# SmartWatch-Basic-Bottom.net
KiCad netlist of a schematic drawn in EAGLE
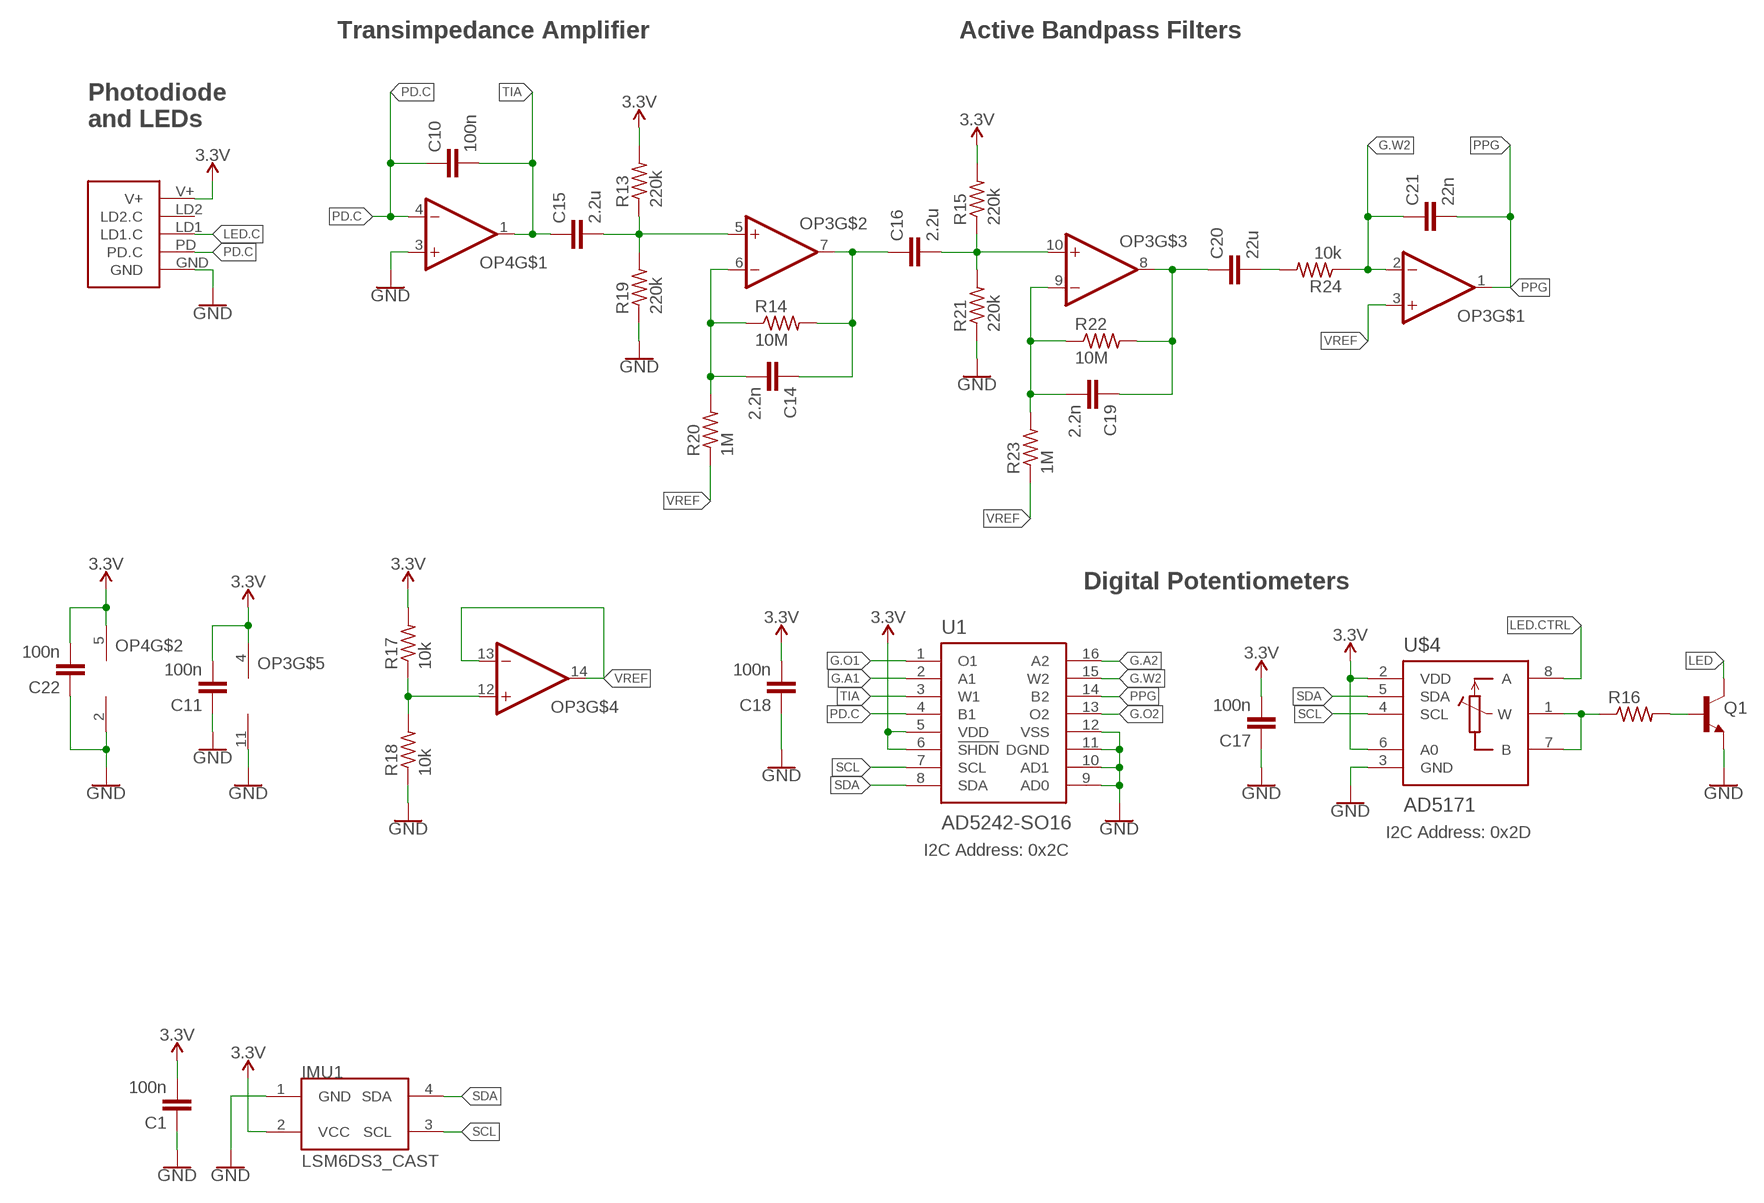
[diagram p0: schematic, sheet 1]

(export (version "E")
  (design (tool "Eeschema 10.0.6"))
  (components
    (comp (ref "C1")
      (value "100n")
      (footprint "eagle-import:C0603")
      (libsource (lib "eagle-import") (part "CAPACITOR0603"))
    )
    (comp (ref "C10")
      (value "100n")
      (footprint "eagle-import:C0603")
      (libsource (lib "eagle-import") (part "CAPACITOR0603"))
    )
    (comp (ref "C11")
      (value "100n")
      (footprint "eagle-import:C0603")
      (libsource (lib "eagle-import") (part "CAPACITOR0603"))
    )
    (comp (ref "C14")
      (value "2.2n")
      (footprint "eagle-import:C0603")
      (libsource (lib "eagle-import") (part "CAPACITOR0603"))
    )
    (comp (ref "C15")
      (value "2.2u")
      (footprint "eagle-import:C0603")
      (libsource (lib "eagle-import") (part "CAPACITOR0603"))
    )
    (comp (ref "C16")
      (value "2.2u")
      (footprint "eagle-import:C0603")
      (libsource (lib "eagle-import") (part "CAPACITOR0603"))
    )
    (comp (ref "C17")
      (value "100n")
      (footprint "eagle-import:C0603")
      (libsource (lib "eagle-import") (part "CAPACITOR0603"))
    )
    (comp (ref "C18")
      (value "100n")
      (footprint "eagle-import:C0603")
      (libsource (lib "eagle-import") (part "CAPACITOR0603"))
    )
    (comp (ref "C19")
      (value "2.2n")
      (footprint "eagle-import:C0603")
      (libsource (lib "eagle-import") (part "CAPACITOR0603"))
    )
    (comp (ref "C20")
      (value "22u")
      (footprint "eagle-import:C0603")
      (libsource (lib "eagle-import") (part "CAPACITOR0603"))
    )
    (comp (ref "C21")
      (value "22n")
      (footprint "eagle-import:C0603")
      (libsource (lib "eagle-import") (part "CAPACITOR0603"))
    )
    (comp (ref "C22")
      (value "100n")
      (footprint "eagle-import:C0603")
      (libsource (lib "eagle-import") (part "CAPACITOR0603"))
    )
    (comp (ref "IMU1")
      (value "LSM6DS3_CAST")
      (footprint "eagle-import:LSM6DS3_CAST")
      (libsource (lib "eagle-import") (part "LSM6DS3_CAST"))
    )
    (comp (ref "OP3")
      (value "OP-QUAD-SO14")
      (footprint "eagle-import:SO14")
      (libsource (lib "eagle-import") (part "OP-QUAD-SO14"))
    )
    (comp (ref "OP4")
      (value "OP-SINGLEOT")
      (footprint "eagle-import:SOT23-5")
      (libsource (lib "eagle-import") (part "OP-SINGLEOT"))
    )
    (comp (ref "Q1")
      (value "NPN-GENERIC")
      (footprint "eagle-import:SOT23-3")
      (libsource (lib "eagle-import") (part "NPN-GENERIC"))
    )
    (comp (ref "R13")
      (value "220k")
      (footprint "eagle-import:R0603")
      (libsource (lib "eagle-import") (part "RESISTOR0603"))
    )
    (comp (ref "R14")
      (value "10M")
      (footprint "eagle-import:R0603")
      (libsource (lib "eagle-import") (part "RESISTOR0603"))
    )
    (comp (ref "R15")
      (value "220k")
      (footprint "eagle-import:R0603")
      (libsource (lib "eagle-import") (part "RESISTOR0603"))
    )
    (comp (ref "R16")
      (value "RESISTOR0603")
      (footprint "eagle-import:R0603")
      (libsource (lib "eagle-import") (part "RESISTOR0603"))
    )
    (comp (ref "R17")
      (value "10k")
      (footprint "eagle-import:R0402")
      (libsource (lib "eagle-import") (part "RESISTOR0402"))
    )
    (comp (ref "R18")
      (value "10k")
      (footprint "eagle-import:R0402")
      (libsource (lib "eagle-import") (part "RESISTOR0402"))
    )
    (comp (ref "R19")
      (value "220k")
      (footprint "eagle-import:R0603")
      (libsource (lib "eagle-import") (part "RESISTOR0603"))
    )
    (comp (ref "R20")
      (value "1M")
      (footprint "eagle-import:R0603")
      (libsource (lib "eagle-import") (part "RESISTOR0603"))
    )
    (comp (ref "R21")
      (value "220k")
      (footprint "eagle-import:R0603")
      (libsource (lib "eagle-import") (part "RESISTOR0603"))
    )
    (comp (ref "R22")
      (value "10M")
      (footprint "eagle-import:R0603")
      (libsource (lib "eagle-import") (part "RESISTOR0603"))
    )
    (comp (ref "R23")
      (value "1M")
      (footprint "eagle-import:R0603")
      (libsource (lib "eagle-import") (part "RESISTOR0603"))
    )
    (comp (ref "R24")
      (value "10k")
      (footprint "eagle-import:R0603")
      (libsource (lib "eagle-import") (part "RESISTOR0603"))
    )
    (comp (ref "U$3")
      (value "PPG.MODULE.2")
      (footprint "eagle-import:PPG.MODULE.2")
      (libsource (lib "eagle-import") (part "PPG.MODULE.2"))
    )
    (comp (ref "U$4")
      (value "AD5171")
      (footprint "eagle-import:SOT-23-8")
      (libsource (lib "eagle-import") (part "AD5171"))
    )
    (comp (ref "U1")
      (value "AD5242-SO16")
      (footprint "eagle-import:SO16")
      (libsource (lib "eagle-import") (part "AD5242-SO16"))
    )
  )
  (nets
    (net (code "1") (name "3.3V") (class "Default")
      (node (ref "C1") (pin "2") (pinfunction "2_2") (pintype "passive"))
      (node (ref "C11") (pin "2") (pinfunction "2_2") (pintype "passive"))
      (node (ref "C17") (pin "2") (pinfunction "2_2") (pintype "passive"))
      (node (ref "C18") (pin "2") (pinfunction "2_2") (pintype "passive"))
      (node (ref "C22") (pin "2") (pinfunction "2_2") (pintype "passive"))
      (node (ref "IMU1") (pin "2") (pinfunction "VCC_2") (pintype "bidirectional"))
      (node (ref "OP3") (pin "4") (pinfunction "V+_4") (pintype "power_in"))
      (node (ref "OP4") (pin "5") (pinfunction "V+_5") (pintype "power_in"))
      (node (ref "R13") (pin "2") (pinfunction "2_2") (pintype "passive"))
      (node (ref "R15") (pin "2") (pinfunction "2_2") (pintype "passive"))
      (node (ref "R17") (pin "2") (pinfunction "2_2") (pintype "passive"))
      (node (ref "U$3") (pin "V+") (pinfunction "V+_V+") (pintype "bidirectional"))
      (node (ref "U$4") (pin "2") (pinfunction "VDD_2") (pintype "bidirectional"))
      (node (ref "U$4") (pin "6") (pinfunction "A0_6") (pintype "bidirectional"))
      (node (ref "U1") (pin "5") (pinfunction "VDD_5") (pintype "bidirectional"))
      (node (ref "U1") (pin "6") (pinfunction "~{SHDN}_6") (pintype "bidirectional"))
    )
    (net (code "2") (name "G.A1") (class "Default")
      (node (ref "U1") (pin "2") (pinfunction "A1_2") (pintype "bidirectional"))
    )
    (net (code "3") (name "G.A2") (class "Default")
      (node (ref "U1") (pin "16") (pinfunction "A2_16") (pintype "bidirectional"))
    )
    (net (code "4") (name "G.O1") (class "Default")
      (node (ref "U1") (pin "1") (pinfunction "O1_1") (pintype "bidirectional"))
    )
    (net (code "5") (name "G.O2") (class "Default")
      (node (ref "U1") (pin "13") (pinfunction "O2_13") (pintype "bidirectional"))
    )
    (net (code "6") (name "G.W2") (class "Default")
      (node (ref "C21") (pin "1") (pinfunction "1_1") (pintype "passive"))
      (node (ref "OP3") (pin "2") (pinfunction "-IN_2") (pintype "input"))
      (node (ref "R24") (pin "1") (pinfunction "1_1") (pintype "passive"))
      (node (ref "U1") (pin "15") (pinfunction "W2_15") (pintype "bidirectional"))
    )
    (net (code "7") (name "GND") (class "Default")
      (node (ref "C1") (pin "1") (pinfunction "1_1") (pintype "passive"))
      (node (ref "C11") (pin "1") (pinfunction "1_1") (pintype "passive"))
      (node (ref "C17") (pin "1") (pinfunction "1_1") (pintype "passive"))
      (node (ref "C18") (pin "1") (pinfunction "1_1") (pintype "passive"))
      (node (ref "C22") (pin "1") (pinfunction "1_1") (pintype "passive"))
      (node (ref "IMU1") (pin "1") (pinfunction "GND_1") (pintype "bidirectional"))
      (node (ref "OP3") (pin "11") (pinfunction "V-_11") (pintype "power_in"))
      (node (ref "OP4") (pin "2") (pinfunction "V-_2") (pintype "power_in"))
      (node (ref "OP4") (pin "3") (pinfunction "+IN_3") (pintype "input"))
      (node (ref "Q1") (pin "2") (pinfunction "E_2") (pintype "passive"))
      (node (ref "R18") (pin "1") (pinfunction "1_1") (pintype "passive"))
      (node (ref "R19") (pin "1") (pinfunction "1_1") (pintype "passive"))
      (node (ref "R21") (pin "1") (pinfunction "1_1") (pintype "passive"))
      (node (ref "U$3") (pin "GND") (pinfunction "GND_GND") (pintype "bidirectional"))
      (node (ref "U$4") (pin "3") (pinfunction "GND_3") (pintype "bidirectional"))
      (node (ref "U1") (pin "10") (pinfunction "AD1_10") (pintype "bidirectional"))
      (node (ref "U1") (pin "11") (pinfunction "DGND_11") (pintype "bidirectional"))
      (node (ref "U1") (pin "12") (pinfunction "VSS_12") (pintype "bidirectional"))
      (node (ref "U1") (pin "9") (pinfunction "AD0_9") (pintype "bidirectional"))
    )
    (net (code "8") (name "LED") (class "Default")
      (node (ref "Q1") (pin "3") (pinfunction "C_3") (pintype "passive"))
    )
    (net (code "9") (name "LED.C") (class "Default")
      (node (ref "U$3") (pin "LD1") (pinfunction "LD1.C_LD1") (pintype "bidirectional"))
    )
    (net (code "10") (name "LED.CTRL") (class "Default")
      (node (ref "U$4") (pin "8") (pinfunction "A_8") (pintype "bidirectional"))
    )
    (net (code "11") (name "Net-(C20-Pad2)") (class "Default")
      (node (ref "C20") (pin "2") (pinfunction "2_2") (pintype "passive"))
      (node (ref "R24") (pin "2") (pinfunction "2_2") (pintype "passive"))
    )
    (net (code "12") (name "Net-(OP3B-+IN)") (class "Default")
      (node (ref "C15") (pin "2") (pinfunction "2_2") (pintype "passive"))
      (node (ref "OP3") (pin "5") (pinfunction "+IN_5") (pintype "input"))
      (node (ref "R13") (pin "1") (pinfunction "1_1") (pintype "passive"))
      (node (ref "R19") (pin "2") (pinfunction "2_2") (pintype "passive"))
    )
    (net (code "13") (name "Net-(OP3B--IN)") (class "Default")
      (node (ref "C14") (pin "2") (pinfunction "2_2") (pintype "passive"))
      (node (ref "OP3") (pin "6") (pinfunction "-IN_6") (pintype "input"))
      (node (ref "R14") (pin "1") (pinfunction "1_1") (pintype "passive"))
      (node (ref "R20") (pin "2") (pinfunction "2_2") (pintype "passive"))
    )
    (net (code "14") (name "Net-(OP3B-OUT)") (class "Default")
      (node (ref "C14") (pin "1") (pinfunction "1_1") (pintype "passive"))
      (node (ref "C16") (pin "1") (pinfunction "1_1") (pintype "passive"))
      (node (ref "OP3") (pin "7") (pinfunction "OUT_7") (pintype "output"))
      (node (ref "R14") (pin "2") (pinfunction "2_2") (pintype "passive"))
    )
    (net (code "15") (name "Net-(OP3C-+IN)") (class "Default")
      (node (ref "C16") (pin "2") (pinfunction "2_2") (pintype "passive"))
      (node (ref "OP3") (pin "10") (pinfunction "+IN_10") (pintype "input"))
      (node (ref "R15") (pin "1") (pinfunction "1_1") (pintype "passive"))
      (node (ref "R21") (pin "2") (pinfunction "2_2") (pintype "passive"))
    )
    (net (code "16") (name "Net-(OP3C--IN)") (class "Default")
      (node (ref "C19") (pin "2") (pinfunction "2_2") (pintype "passive"))
      (node (ref "OP3") (pin "9") (pinfunction "-IN_9") (pintype "input"))
      (node (ref "R22") (pin "1") (pinfunction "1_1") (pintype "passive"))
      (node (ref "R23") (pin "2") (pinfunction "2_2") (pintype "passive"))
    )
    (net (code "17") (name "Net-(OP3C-OUT)") (class "Default")
      (node (ref "C19") (pin "1") (pinfunction "1_1") (pintype "passive"))
      (node (ref "C20") (pin "1") (pinfunction "1_1") (pintype "passive"))
      (node (ref "OP3") (pin "8") (pinfunction "OUT_8") (pintype "output"))
      (node (ref "R22") (pin "2") (pinfunction "2_2") (pintype "passive"))
    )
    (net (code "18") (name "Net-(OP3D-+IN)") (class "Default")
      (node (ref "OP3") (pin "12") (pinfunction "+IN_12") (pintype "input"))
      (node (ref "R17") (pin "1") (pinfunction "1_1") (pintype "passive"))
      (node (ref "R18") (pin "2") (pinfunction "2_2") (pintype "passive"))
    )
    (net (code "19") (name "Net-(Q1-B)") (class "Default")
      (node (ref "Q1") (pin "1") (pinfunction "B_1") (pintype "passive"))
      (node (ref "R16") (pin "2") (pinfunction "2_2") (pintype "passive"))
    )
    (net (code "20") (name "Net-(U$4-B)") (class "Default")
      (node (ref "R16") (pin "1") (pinfunction "1_1") (pintype "passive"))
      (node (ref "U$4") (pin "1") (pinfunction "W_1") (pintype "bidirectional"))
      (node (ref "U$4") (pin "7") (pinfunction "B_7") (pintype "bidirectional"))
    )
    (net (code "21") (name "PD.C") (class "Default")
      (node (ref "C10") (pin "1") (pinfunction "1_1") (pintype "passive"))
      (node (ref "OP4") (pin "4") (pinfunction "-IN_4") (pintype "input"))
      (node (ref "U$3") (pin "PD") (pinfunction "PD.C_PD") (pintype "bidirectional"))
      (node (ref "U1") (pin "4") (pinfunction "B1_4") (pintype "bidirectional"))
    )
    (net (code "22") (name "PPG") (class "Default")
      (node (ref "C21") (pin "2") (pinfunction "2_2") (pintype "passive"))
      (node (ref "OP3") (pin "1") (pinfunction "OUT_1") (pintype "output"))
      (node (ref "U1") (pin "14") (pinfunction "B2_14") (pintype "bidirectional"))
    )
    (net (code "23") (name "SCL") (class "Default")
      (node (ref "IMU1") (pin "3") (pinfunction "SCL_3") (pintype "bidirectional"))
      (node (ref "U$4") (pin "4") (pinfunction "SCL_4") (pintype "bidirectional"))
      (node (ref "U1") (pin "7") (pinfunction "SCL_7") (pintype "bidirectional"))
    )
    (net (code "24") (name "SDA") (class "Default")
      (node (ref "IMU1") (pin "4") (pinfunction "SDA_4") (pintype "bidirectional"))
      (node (ref "U$4") (pin "5") (pinfunction "SDA_5") (pintype "bidirectional"))
      (node (ref "U1") (pin "8") (pinfunction "SDA_8") (pintype "bidirectional"))
    )
    (net (code "25") (name "TIA") (class "Default")
      (node (ref "C10") (pin "2") (pinfunction "2_2") (pintype "passive"))
      (node (ref "C15") (pin "1") (pinfunction "1_1") (pintype "passive"))
      (node (ref "OP4") (pin "1") (pinfunction "OUT_1") (pintype "output"))
      (node (ref "U1") (pin "3") (pinfunction "W1_3") (pintype "bidirectional"))
    )
    (net (code "26") (name "VREF") (class "Default")
      (node (ref "OP3") (pin "13") (pinfunction "-IN_13") (pintype "input"))
      (node (ref "OP3") (pin "14") (pinfunction "OUT_14") (pintype "output"))
      (node (ref "OP3") (pin "3") (pinfunction "+IN_3") (pintype "input"))
      (node (ref "R20") (pin "1") (pinfunction "1_1") (pintype "passive"))
      (node (ref "R23") (pin "1") (pinfunction "1_1") (pintype "passive"))
    )
    (net (code "27") (name "unconnected-(U$3-LD2.C-PadLD2)") (class "Default")
      (node (ref "U$3") (pin "LD2") (pinfunction "LD2.C_LD2") (pintype "bidirectional"))
    )
  )
)
